# PracticeBoardV1.net
KiCad netlist of a schematic drawn in EAGLE
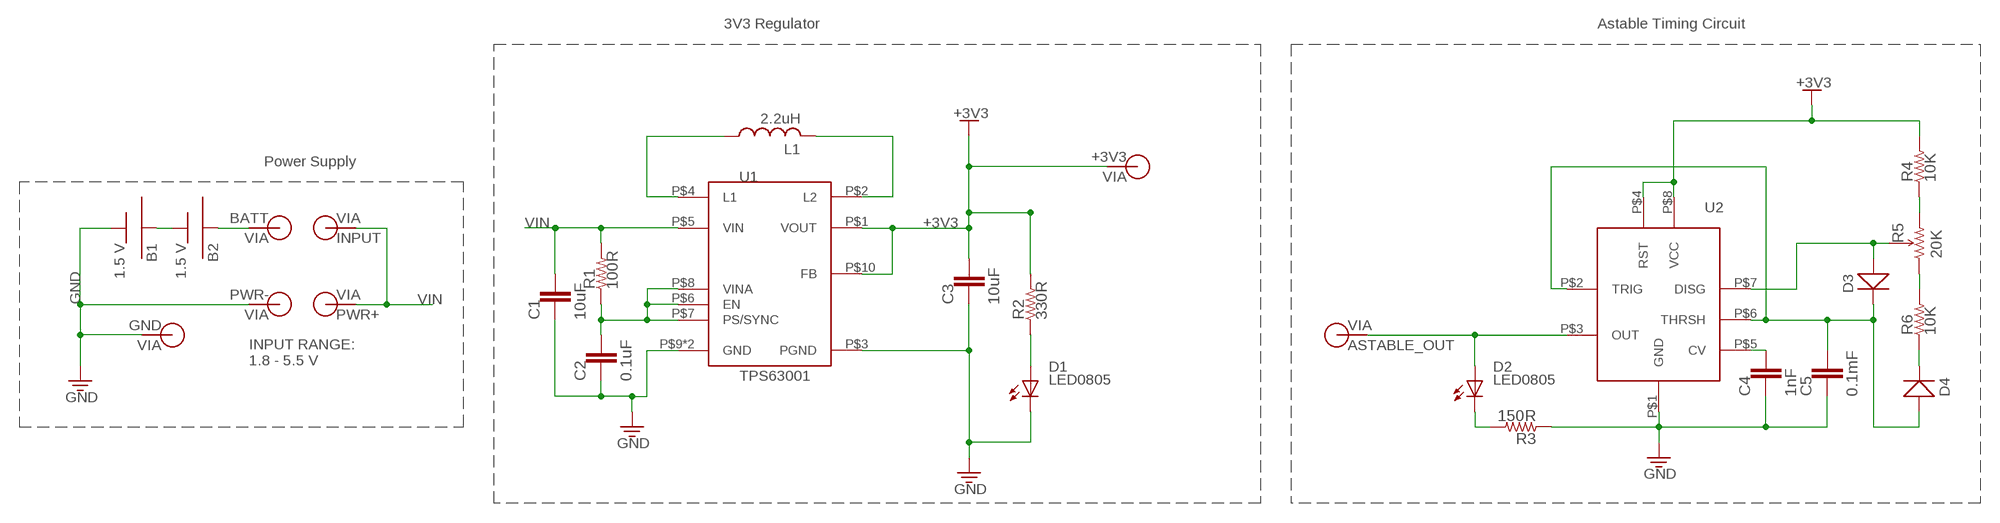
[diagram p0: schematic, sheet 1, part 1 of 2]
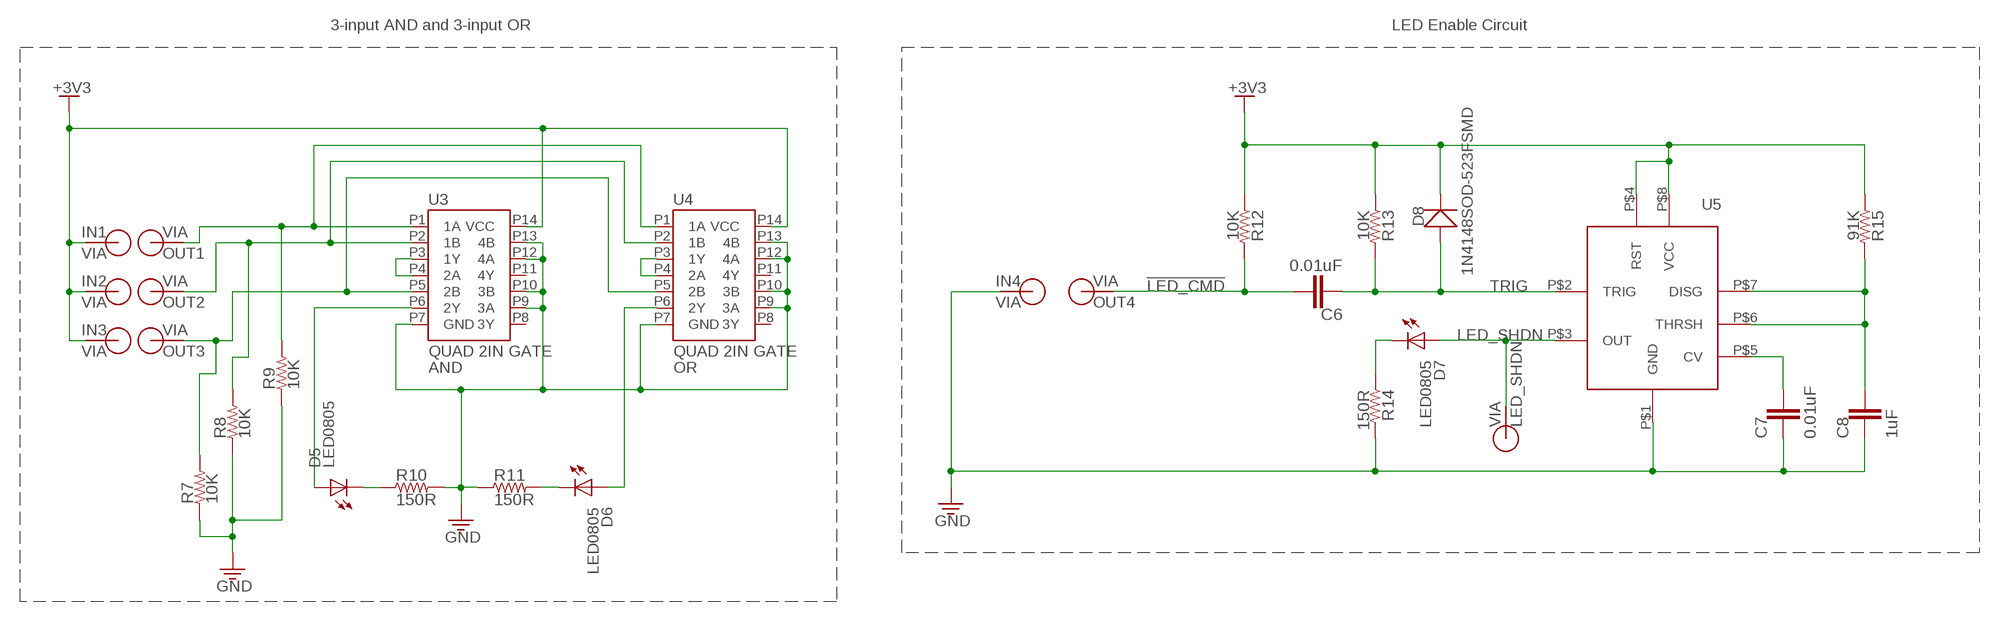
[diagram p1: schematic, sheet 1, part 2 of 2]

(export (version "E")
  (design (tool "Eeschema 10.0.6"))
  (components
    (comp (ref "B1")
      (value "1.5 V")
      (footprint "eagle-import:BCAAPC-BATT-HOLDER")
      (libsource (lib "eagle-import") (part "BCAAPC-BATT-HOLDER"))
    )
    (comp (ref "B2")
      (value "1.5 V")
      (footprint "eagle-import:BCAAPC-BATT-HOLDER")
      (libsource (lib "eagle-import") (part "BCAAPC-BATT-HOLDER"))
    )
    (comp (ref "C1")
      (value "10uF")
      (footprint "eagle-import:0805")
      (libsource (lib "eagle-import") (part "CAP0805"))
    )
    (comp (ref "C2")
      (value "0.1uF")
      (footprint "eagle-import:0805")
      (libsource (lib "eagle-import") (part "CAP0805"))
    )
    (comp (ref "C3")
      (value "10uF")
      (footprint "eagle-import:0805")
      (libsource (lib "eagle-import") (part "CAP0805"))
    )
    (comp (ref "C4")
      (value "1nF")
      (footprint "eagle-import:0805")
      (libsource (lib "eagle-import") (part "CAP0805"))
    )
    (comp (ref "C5")
      (value "0.1mF")
      (footprint "eagle-import:0805")
      (libsource (lib "eagle-import") (part "CAP0805"))
    )
    (comp (ref "C6")
      (value "0.01uF")
      (footprint "eagle-import:0805")
      (libsource (lib "eagle-import") (part "CAP0805"))
    )
    (comp (ref "C7")
      (value "0.01uF")
      (footprint "eagle-import:0805")
      (libsource (lib "eagle-import") (part "CAP0805"))
    )
    (comp (ref "C8")
      (value "1uF")
      (footprint "eagle-import:0805")
      (libsource (lib "eagle-import") (part "CAP0805"))
    )
    (comp (ref "D1")
      (value "LED0805")
      (footprint "eagle-import:0805-D")
      (libsource (lib "eagle-import") (part "LED0805"))
    )
    (comp (ref "D2")
      (value "LED0805")
      (footprint "eagle-import:0805-D")
      (libsource (lib "eagle-import") (part "LED0805"))
    )
    (comp (ref "D3")
      (value "1N4148THRU-HOLE")
      (footprint "eagle-import:1N4148")
      (libsource (lib "eagle-import") (part "1N4148THRU-HOLE"))
    )
    (comp (ref "D4")
      (value "1N4148THRU-HOLE")
      (footprint "eagle-import:1N4148")
      (libsource (lib "eagle-import") (part "1N4148THRU-HOLE"))
    )
    (comp (ref "D5")
      (value "LED0805")
      (footprint "eagle-import:0805-D")
      (libsource (lib "eagle-import") (part "LED0805"))
    )
    (comp (ref "D6")
      (value "LED0805")
      (footprint "eagle-import:0805-D")
      (libsource (lib "eagle-import") (part "LED0805"))
    )
    (comp (ref "D7")
      (value "LED0805")
      (footprint "eagle-import:0805-D")
      (libsource (lib "eagle-import") (part "LED0805"))
    )
    (comp (ref "D8")
      (value "1N4148SOD-523FSMD")
      (footprint "eagle-import:SOD-523F")
      (libsource (lib "eagle-import") (part "1N4148SMDSOD-523F"))
    )
    (comp (ref "L1")
      (value "2.2uH")
      (footprint "eagle-import:L3225M")
      (libsource (lib "eagle-import") (part "L-USL3225M"))
    )
    (comp (ref "R1")
      (value "100R")
      (footprint "eagle-import:0805")
      (libsource (lib "eagle-import") (part "RES0805"))
    )
    (comp (ref "R2")
      (value "330R")
      (footprint "eagle-import:0805")
      (libsource (lib "eagle-import") (part "RES0805"))
    )
    (comp (ref "R3")
      (value "150R")
      (footprint "eagle-import:0805")
      (libsource (lib "eagle-import") (part "RES0805"))
    )
    (comp (ref "R4")
      (value "10K")
      (footprint "eagle-import:0805")
      (libsource (lib "eagle-import") (part "RES0805"))
    )
    (comp (ref "R5")
      (value "20K")
      (footprint "eagle-import:P160KN")
      (libsource (lib "eagle-import") (part "P160KN-0QC15B20K-POT"))
    )
    (comp (ref "R6")
      (value "10K")
      (footprint "eagle-import:0805")
      (libsource (lib "eagle-import") (part "RES0805"))
    )
    (comp (ref "R7")
      (value "10K")
      (footprint "eagle-import:0805")
      (libsource (lib "eagle-import") (part "RES0805"))
    )
    (comp (ref "R8")
      (value "10K")
      (footprint "eagle-import:0805")
      (libsource (lib "eagle-import") (part "RES0805"))
    )
    (comp (ref "R9")
      (value "10K")
      (footprint "eagle-import:0805")
      (libsource (lib "eagle-import") (part "RES0805"))
    )
    (comp (ref "R10")
      (value "150R")
      (footprint "eagle-import:0805")
      (libsource (lib "eagle-import") (part "RES0805"))
    )
    (comp (ref "R11")
      (value "150R")
      (footprint "eagle-import:0805")
      (libsource (lib "eagle-import") (part "RES0805"))
    )
    (comp (ref "R12")
      (value "10K")
      (footprint "eagle-import:0805")
      (libsource (lib "eagle-import") (part "RES0805"))
    )
    (comp (ref "R13")
      (value "10K")
      (footprint "eagle-import:0805")
      (libsource (lib "eagle-import") (part "RES0805"))
    )
    (comp (ref "R14")
      (value "150R")
      (footprint "eagle-import:0805")
      (libsource (lib "eagle-import") (part "RES0805"))
    )
    (comp (ref "R15")
      (value "91K")
      (footprint "eagle-import:0805")
      (libsource (lib "eagle-import") (part "RES0805"))
    )
    (comp (ref "U1")
      (value "TPS63001")
      (footprint "eagle-import:QFN10_POWERPAD")
      (libsource (lib "eagle-import") (part "TPS6300X"))
    )
    (comp (ref "U2")
      (value "TLC555")
      (footprint "eagle-import:SO-8")
      (libsource (lib "eagle-import") (part "TLC555"))
    )
    (comp (ref "U3")
      (value "AND")
      (footprint "eagle-import:VQFN-14")
      (libsource (lib "eagle-import") (part "QUAD-2IN-GATE-AND-SN74AHC08RGYR"))
    )
    (comp (ref "U4")
      (value "OR")
      (footprint "eagle-import:TSSOP-14")
      (libsource (lib "eagle-import") (part "QUAD-2IN-GATE-OR-SN74LV32APWRG4"))
    )
    (comp (ref "U5")
      (value "TLC555")
      (footprint "eagle-import:SO-8")
      (libsource (lib "eagle-import") (part "TLC555"))
    )
    (comp (ref "V1")
      (value "BATT")
      (footprint "eagle-import:VIA-60MIL-SQ")
      (libsource (lib "eagle-import") (part "VIA60MIL-SQ"))
    )
    (comp (ref "V2")
      (value "PWR-")
      (footprint "eagle-import:VIA-60MIL-SQ")
      (libsource (lib "eagle-import") (part "VIA60MIL-SQ"))
    )
    (comp (ref "V3")
      (value "INPUT")
      (footprint "eagle-import:VIA-60MIL-SQ")
      (libsource (lib "eagle-import") (part "VIA60MIL-SQ"))
    )
    (comp (ref "V4")
      (value "PWR+")
      (footprint "eagle-import:VIA-60MIL-SQ")
      (libsource (lib "eagle-import") (part "VIA60MIL-SQ"))
    )
    (comp (ref "V5")
      (value "+3V3")
      (footprint "eagle-import:VIA-60MIL-SQ")
      (libsource (lib "eagle-import") (part "VIA60MIL-SQ"))
    )
    (comp (ref "V6")
      (value "ASTABLE_OUT")
      (footprint "eagle-import:VIA-60MIL-SQ")
      (libsource (lib "eagle-import") (part "VIA60MIL-SQ"))
    )
    (comp (ref "V7")
      (value "IN1")
      (footprint "eagle-import:VIA-60MIL-SQ")
      (libsource (lib "eagle-import") (part "VIA60MIL-SQ"))
    )
    (comp (ref "V8")
      (value "IN2")
      (footprint "eagle-import:VIA-60MIL-SQ")
      (libsource (lib "eagle-import") (part "VIA60MIL-SQ"))
    )
    (comp (ref "V9")
      (value "IN3")
      (footprint "eagle-import:VIA-60MIL-SQ")
      (libsource (lib "eagle-import") (part "VIA60MIL-SQ"))
    )
    (comp (ref "V10")
      (value "OUT1")
      (footprint "eagle-import:VIA-60MIL-SQ")
      (libsource (lib "eagle-import") (part "VIA60MIL-SQ"))
    )
    (comp (ref "V11")
      (value "OUT2")
      (footprint "eagle-import:VIA-60MIL-SQ")
      (libsource (lib "eagle-import") (part "VIA60MIL-SQ"))
    )
    (comp (ref "V12")
      (value "OUT3")
      (footprint "eagle-import:VIA-60MIL-SQ")
      (libsource (lib "eagle-import") (part "VIA60MIL-SQ"))
    )
    (comp (ref "V13")
      (value "IN4")
      (footprint "eagle-import:VIA-60MIL-SQ")
      (libsource (lib "eagle-import") (part "VIA60MIL-SQ"))
    )
    (comp (ref "V14")
      (value "OUT4")
      (footprint "eagle-import:VIA-60MIL-SQ")
      (libsource (lib "eagle-import") (part "VIA60MIL-SQ"))
    )
    (comp (ref "V15")
      (value "LED_SHDN")
      (footprint "eagle-import:VIA-60MIL-SQ")
      (libsource (lib "eagle-import") (part "VIA60MIL-SQ"))
    )
    (comp (ref "V16")
      (value "GND")
      (footprint "eagle-import:VIA-60MIL-SQ")
      (libsource (lib "eagle-import") (part "VIA60MIL-SQ"))
    )
  )
  (nets
    (net (code "1") (name "+3V3") (class "Default")
      (node (ref "C3") (pin "1") (pinfunction "P$1_1") (pintype "passive"))
      (node (ref "D8") (pin "C") (pinfunction "C_C") (pintype "bidirectional"))
      (node (ref "R12") (pin "1") (pinfunction "1_1") (pintype "passive"))
      (node (ref "R13") (pin "1") (pinfunction "1_1") (pintype "passive"))
      (node (ref "R15") (pin "1") (pinfunction "1_1") (pintype "passive"))
      (node (ref "R2") (pin "2") (pinfunction "2_2") (pintype "passive"))
      (node (ref "R4") (pin "2") (pinfunction "2_2") (pintype "passive"))
      (node (ref "U1") (pin "P$1") (pinfunction "VOUT_P$1") (pintype "output"))
      (node (ref "U1") (pin "P$10") (pinfunction "FB_P$10") (pintype "input"))
      (node (ref "U2") (pin "P$4") (pinfunction "RST_P$4") (pintype "bidirectional"))
      (node (ref "U2") (pin "P$8") (pinfunction "VCC_P$8") (pintype "bidirectional"))
      (node (ref "U3") (pin "P14") (pinfunction "VCC_P14") (pintype "bidirectional"))
      (node (ref "U4") (pin "P14") (pinfunction "VCC_P14") (pintype "bidirectional"))
      (node (ref "U5") (pin "P$4") (pinfunction "RST_P$4") (pintype "bidirectional"))
      (node (ref "U5") (pin "P$8") (pinfunction "VCC_P$8") (pintype "bidirectional"))
      (node (ref "V5") (pin "P$1") (pinfunction "P$1_P$1") (pintype "bidirectional"))
      (node (ref "V7") (pin "P$1") (pinfunction "P$1_P$1") (pintype "bidirectional"))
      (node (ref "V8") (pin "P$1") (pinfunction "P$1_P$1") (pintype "bidirectional"))
      (node (ref "V9") (pin "P$1") (pinfunction "P$1_P$1") (pintype "bidirectional"))
    )
    (net (code "2") (name "/LED_SHDN") (class "Default")
      (node (ref "D7") (pin "A") (pinfunction "A_A") (pintype "passive"))
      (node (ref "U5") (pin "P$3") (pinfunction "OUT_P$3") (pintype "bidirectional"))
      (node (ref "V15") (pin "P$1") (pinfunction "P$1_P$1") (pintype "bidirectional"))
    )
    (net (code "3") (name "/TRIG") (class "Default")
      (node (ref "C6") (pin "2") (pinfunction "P$2_2") (pintype "passive"))
      (node (ref "D8") (pin "A") (pinfunction "A_A") (pintype "bidirectional"))
      (node (ref "R13") (pin "2") (pinfunction "2_2") (pintype "passive"))
      (node (ref "U5") (pin "P$2") (pinfunction "TRIG_P$2") (pintype "bidirectional"))
    )
    (net (code "4") (name "/VIN") (class "Default")
      (node (ref "C1") (pin "1") (pinfunction "P$1_1") (pintype "passive"))
      (node (ref "R1") (pin "2") (pinfunction "2_2") (pintype "passive"))
      (node (ref "U1") (pin "P$5") (pinfunction "VIN_P$5") (pintype "input"))
      (node (ref "V3") (pin "P$1") (pinfunction "P$1_P$1") (pintype "bidirectional"))
      (node (ref "V4") (pin "P$1") (pinfunction "P$1_P$1") (pintype "bidirectional"))
    )
    (net (code "5") (name "/~{LED_CMD}") (class "Default")
      (node (ref "C6") (pin "1") (pinfunction "P$1_1") (pintype "passive"))
      (node (ref "R12") (pin "2") (pinfunction "2_2") (pintype "passive"))
      (node (ref "V14") (pin "P$1") (pinfunction "P$1_P$1") (pintype "bidirectional"))
    )
    (net (code "6") (name "GND") (class "Default")
      (node (ref "B1") (pin "MINUS") (pinfunction "MINUS_MINUS") (pintype "power_in"))
      (node (ref "C1") (pin "2") (pinfunction "P$2_2") (pintype "passive"))
      (node (ref "C2") (pin "2") (pinfunction "P$2_2") (pintype "passive"))
      (node (ref "C3") (pin "2") (pinfunction "P$2_2") (pintype "passive"))
      (node (ref "C4") (pin "2") (pinfunction "P$2_2") (pintype "passive"))
      (node (ref "C5") (pin "2") (pinfunction "P$2_2") (pintype "passive"))
      (node (ref "C7") (pin "2") (pinfunction "P$2_2") (pintype "passive"))
      (node (ref "C8") (pin "2") (pinfunction "P$2_2") (pintype "passive"))
      (node (ref "D1") (pin "C") (pinfunction "C_C") (pintype "passive"))
      (node (ref "R10") (pin "2") (pinfunction "2_2") (pintype "passive"))
      (node (ref "R11") (pin "1") (pinfunction "1_1") (pintype "passive"))
      (node (ref "R14") (pin "2") (pinfunction "2_2") (pintype "passive"))
      (node (ref "R3") (pin "1") (pinfunction "1_1") (pintype "passive"))
      (node (ref "R7") (pin "1") (pinfunction "1_1") (pintype "passive"))
      (node (ref "R8") (pin "1") (pinfunction "1_1") (pintype "passive"))
      (node (ref "R9") (pin "1") (pinfunction "1_1") (pintype "passive"))
      (node (ref "U1") (pin "P$3") (pinfunction "PGND_P$3") (pintype "input"))
      (node (ref "U1") (pin "P$9") (pinfunction "GND_P$9") (pintype "input"))
      (node (ref "U1") (pin "PAD") (pinfunction "GND_PAD") (pintype "input"))
      (node (ref "U2") (pin "P$1") (pinfunction "GND_P$1") (pintype "bidirectional"))
      (node (ref "U3") (pin "P10") (pinfunction "3B_P10") (pintype "bidirectional"))
      (node (ref "U3") (pin "P12") (pinfunction "4A_P12") (pintype "bidirectional"))
      (node (ref "U3") (pin "P13") (pinfunction "4B_P13") (pintype "bidirectional"))
      (node (ref "U3") (pin "P7") (pinfunction "GND_P7") (pintype "bidirectional"))
      (node (ref "U3") (pin "P9") (pinfunction "3A_P9") (pintype "bidirectional"))
      (node (ref "U4") (pin "P10") (pinfunction "3B_P10") (pintype "bidirectional"))
      (node (ref "U4") (pin "P12") (pinfunction "4A_P12") (pintype "bidirectional"))
      (node (ref "U4") (pin "P13") (pinfunction "4B_P13") (pintype "bidirectional"))
      (node (ref "U4") (pin "P7") (pinfunction "GND_P7") (pintype "bidirectional"))
      (node (ref "U4") (pin "P9") (pinfunction "3A_P9") (pintype "bidirectional"))
      (node (ref "U5") (pin "P$1") (pinfunction "GND_P$1") (pintype "bidirectional"))
      (node (ref "V13") (pin "P$1") (pinfunction "P$1_P$1") (pintype "bidirectional"))
      (node (ref "V16") (pin "P$1") (pinfunction "P$1_P$1") (pintype "bidirectional"))
      (node (ref "V2") (pin "P$1") (pinfunction "P$1_P$1") (pintype "bidirectional"))
    )
    (net (code "7") (name "Net-(B1-PadPLUS)") (class "Default")
      (node (ref "B1") (pin "PLUS") (pinfunction "PLUS_PLUS") (pintype "power_in"))
      (node (ref "B2") (pin "MINUS") (pinfunction "MINUS_MINUS") (pintype "power_in"))
    )
    (net (code "8") (name "Net-(B2-PadPLUS)") (class "Default")
      (node (ref "B2") (pin "PLUS") (pinfunction "PLUS_PLUS") (pintype "power_in"))
      (node (ref "V1") (pin "P$1") (pinfunction "P$1_P$1") (pintype "bidirectional"))
    )
    (net (code "9") (name "Net-(C2-P$1)") (class "Default")
      (node (ref "C2") (pin "1") (pinfunction "P$1_1") (pintype "passive"))
      (node (ref "R1") (pin "1") (pinfunction "1_1") (pintype "passive"))
      (node (ref "U1") (pin "P$6") (pinfunction "EN_P$6") (pintype "input"))
      (node (ref "U1") (pin "P$7") (pinfunction "PS/SYNC_P$7") (pintype "input"))
      (node (ref "U1") (pin "P$8") (pinfunction "VINA_P$8") (pintype "input"))
    )
    (net (code "10") (name "Net-(C4-P$1)") (class "Default")
      (node (ref "C4") (pin "1") (pinfunction "P$1_1") (pintype "passive"))
      (node (ref "U2") (pin "P$5") (pinfunction "CV_P$5") (pintype "bidirectional"))
    )
    (net (code "11") (name "Net-(C5-P$1)") (class "Default")
      (node (ref "C5") (pin "1") (pinfunction "P$1_1") (pintype "passive"))
      (node (ref "D3") (pin "C") (pinfunction "C_C") (pintype "bidirectional"))
      (node (ref "D4") (pin "A") (pinfunction "A_A") (pintype "bidirectional"))
      (node (ref "U2") (pin "P$2") (pinfunction "TRIG_P$2") (pintype "bidirectional"))
      (node (ref "U2") (pin "P$6") (pinfunction "THRSH_P$6") (pintype "bidirectional"))
    )
    (net (code "12") (name "Net-(C7-P$1)") (class "Default")
      (node (ref "C7") (pin "1") (pinfunction "P$1_1") (pintype "passive"))
      (node (ref "U5") (pin "P$5") (pinfunction "CV_P$5") (pintype "bidirectional"))
    )
    (net (code "13") (name "Net-(C8-P$1)") (class "Default")
      (node (ref "C8") (pin "1") (pinfunction "P$1_1") (pintype "passive"))
      (node (ref "R15") (pin "2") (pinfunction "2_2") (pintype "passive"))
      (node (ref "U5") (pin "P$6") (pinfunction "THRSH_P$6") (pintype "bidirectional"))
      (node (ref "U5") (pin "P$7") (pinfunction "DISG_P$7") (pintype "bidirectional"))
    )
    (net (code "14") (name "Net-(D1-PadA)") (class "Default")
      (node (ref "D1") (pin "A") (pinfunction "A_A") (pintype "passive"))
      (node (ref "R2") (pin "1") (pinfunction "1_1") (pintype "passive"))
    )
    (net (code "15") (name "Net-(D2-PadC)") (class "Default")
      (node (ref "D2") (pin "C") (pinfunction "C_C") (pintype "passive"))
      (node (ref "R3") (pin "2") (pinfunction "2_2") (pintype "passive"))
    )
    (net (code "16") (name "Net-(D4-PadC)") (class "Default")
      (node (ref "D4") (pin "C") (pinfunction "C_C") (pintype "bidirectional"))
      (node (ref "R6") (pin "1") (pinfunction "1_1") (pintype "passive"))
    )
    (net (code "17") (name "Net-(D5-PadC)") (class "Default")
      (node (ref "D5") (pin "C") (pinfunction "C_C") (pintype "passive"))
      (node (ref "R10") (pin "1") (pinfunction "1_1") (pintype "passive"))
    )
    (net (code "18") (name "Net-(D6-PadC)") (class "Default")
      (node (ref "D6") (pin "C") (pinfunction "C_C") (pintype "passive"))
      (node (ref "R11") (pin "2") (pinfunction "2_2") (pintype "passive"))
    )
    (net (code "19") (name "Net-(D7-PadC)") (class "Default")
      (node (ref "D7") (pin "C") (pinfunction "C_C") (pintype "passive"))
      (node (ref "R14") (pin "1") (pinfunction "1_1") (pintype "passive"))
    )
    (net (code "20") (name "Net-(R5-1)") (class "Default")
      (node (ref "R5") (pin "P1") (pinfunction "1_P1") (pintype "bidirectional"))
      (node (ref "R6") (pin "2") (pinfunction "2_2") (pintype "passive"))
    )
    (net (code "21") (name "Net-(R5-2)") (class "Default")
      (node (ref "R4") (pin "1") (pinfunction "1_1") (pintype "passive"))
      (node (ref "R5") (pin "P2") (pinfunction "2_P2") (pintype "bidirectional"))
    )
    (net (code "22") (name "Net-(R5-P$1)") (class "Default")
      (node (ref "D3") (pin "A") (pinfunction "A_A") (pintype "bidirectional"))
      (node (ref "R5") (pin "P3") (pinfunction "P$1_P3") (pintype "bidirectional"))
      (node (ref "U2") (pin "P$7") (pinfunction "DISG_P$7") (pintype "bidirectional"))
    )
    (net (code "23") (name "Net-(U1-L1)") (class "Default")
      (node (ref "L1") (pin "1") (pinfunction "1_1") (pintype "passive"))
      (node (ref "U1") (pin "P$4") (pinfunction "L1_P$4") (pintype "input"))
    )
    (net (code "24") (name "Net-(U1-L2)") (class "Default")
      (node (ref "L1") (pin "2") (pinfunction "2_2") (pintype "passive"))
      (node (ref "U1") (pin "P$2") (pinfunction "L2_P$2") (pintype "input"))
    )
    (net (code "25") (name "Net-(U2-OUT)") (class "Default")
      (node (ref "D2") (pin "A") (pinfunction "A_A") (pintype "passive"))
      (node (ref "U2") (pin "P$3") (pinfunction "OUT_P$3") (pintype "bidirectional"))
      (node (ref "V6") (pin "P$1") (pinfunction "P$1_P$1") (pintype "bidirectional"))
    )
    (net (code "26") (name "Net-(U3-1A)") (class "Default")
      (node (ref "R9") (pin "2") (pinfunction "2_2") (pintype "passive"))
      (node (ref "U3") (pin "P1") (pinfunction "1A_P1") (pintype "bidirectional"))
      (node (ref "U4") (pin "P1") (pinfunction "1A_P1") (pintype "bidirectional"))
      (node (ref "V10") (pin "P$1") (pinfunction "P$1_P$1") (pintype "bidirectional"))
    )
    (net (code "27") (name "Net-(U3-1B)") (class "Default")
      (node (ref "R8") (pin "2") (pinfunction "2_2") (pintype "passive"))
      (node (ref "U3") (pin "P2") (pinfunction "1B_P2") (pintype "bidirectional"))
      (node (ref "U4") (pin "P2") (pinfunction "1B_P2") (pintype "bidirectional"))
      (node (ref "V11") (pin "P$1") (pinfunction "P$1_P$1") (pintype "bidirectional"))
    )
    (net (code "28") (name "Net-(U3-1Y)") (class "Default")
      (node (ref "U3") (pin "P3") (pinfunction "1Y_P3") (pintype "bidirectional"))
      (node (ref "U3") (pin "P4") (pinfunction "2A_P4") (pintype "bidirectional"))
    )
    (net (code "29") (name "Net-(U3-2B)") (class "Default")
      (node (ref "R7") (pin "2") (pinfunction "2_2") (pintype "passive"))
      (node (ref "U3") (pin "P5") (pinfunction "2B_P5") (pintype "bidirectional"))
      (node (ref "U4") (pin "P5") (pinfunction "2B_P5") (pintype "bidirectional"))
      (node (ref "V12") (pin "P$1") (pinfunction "P$1_P$1") (pintype "bidirectional"))
    )
    (net (code "30") (name "Net-(U3-2Y)") (class "Default")
      (node (ref "D5") (pin "A") (pinfunction "A_A") (pintype "passive"))
      (node (ref "U3") (pin "P6") (pinfunction "2Y_P6") (pintype "bidirectional"))
    )
    (net (code "31") (name "Net-(U4-1Y)") (class "Default")
      (node (ref "U4") (pin "P3") (pinfunction "1Y_P3") (pintype "bidirectional"))
      (node (ref "U4") (pin "P4") (pinfunction "2A_P4") (pintype "bidirectional"))
    )
    (net (code "32") (name "Net-(U4-2Y)") (class "Default")
      (node (ref "D6") (pin "A") (pinfunction "A_A") (pintype "passive"))
      (node (ref "U4") (pin "P6") (pinfunction "2Y_P6") (pintype "bidirectional"))
    )
    (net (code "33") (name "unconnected-(U3-3Y-PadP8)") (class "Default")
      (node (ref "U3") (pin "P8") (pinfunction "3Y_P8") (pintype "bidirectional"))
    )
    (net (code "34") (name "unconnected-(U3-4Y-PadP11)") (class "Default")
      (node (ref "U3") (pin "P11") (pinfunction "4Y_P11") (pintype "bidirectional"))
    )
    (net (code "35") (name "unconnected-(U4-3Y-PadP8)") (class "Default")
      (node (ref "U4") (pin "P8") (pinfunction "3Y_P8") (pintype "bidirectional"))
    )
    (net (code "36") (name "unconnected-(U4-4Y-PadP11)") (class "Default")
      (node (ref "U4") (pin "P11") (pinfunction "4Y_P11") (pintype "bidirectional"))
    )
  )
)
